# rapidshark-display-shifter-mk-2_0.net
KiCad netlist of a schematic drawn in EAGLE
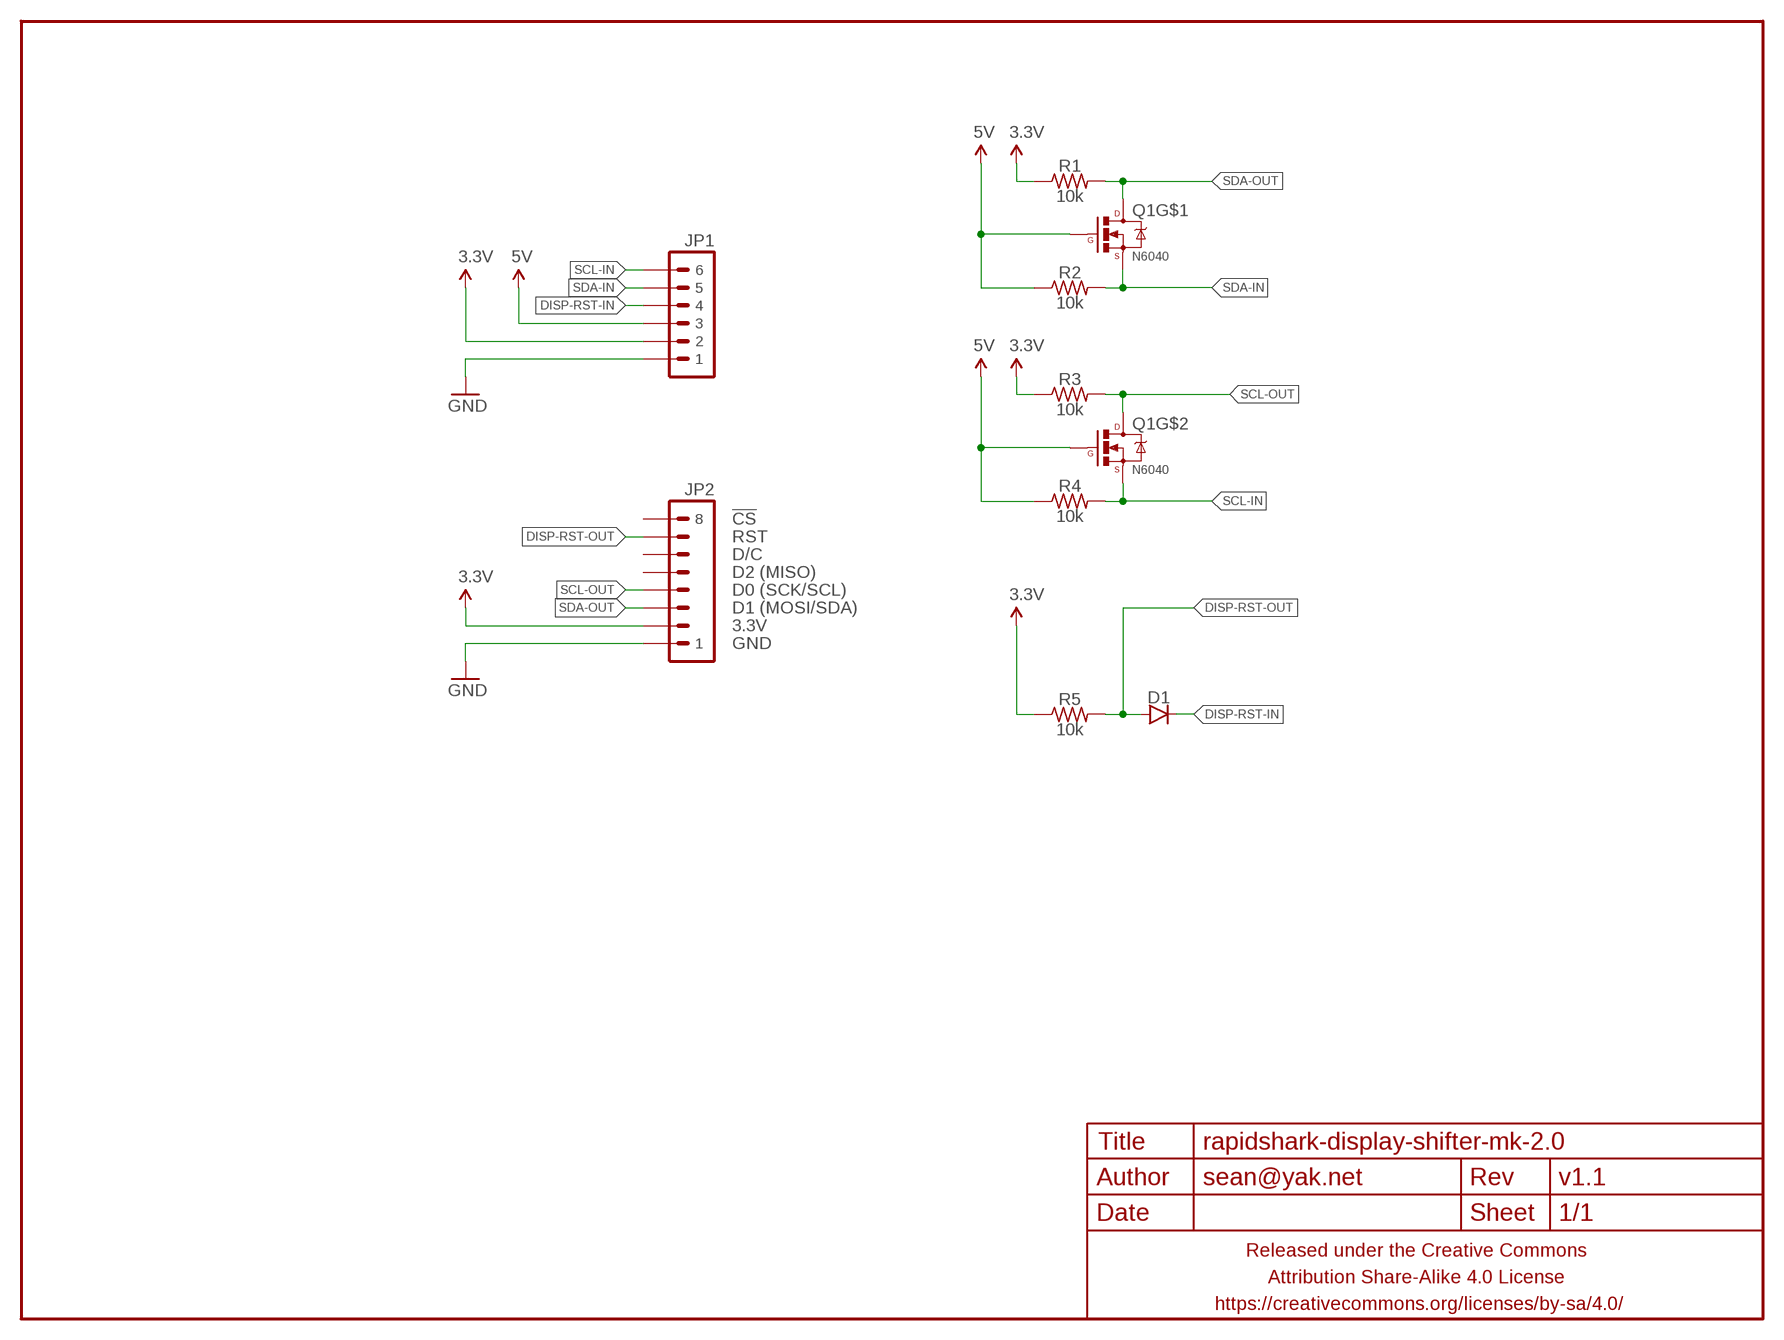
[diagram p0: schematic, sheet 1]

(export (version "E")
  (design (tool "Eeschema 10.0.6"))
  (components
    (comp (ref "D1")
      (value "DIODESMA")
      (footprint "eagle-import:SMA-DIODE")
      (libsource (lib "eagle-import") (part "DIODESMA"))
    )
    (comp (ref "FRAME1")
      (value "FRAME-LETTERNO_PACKAGE")
      (footprint "eagle-import:DUMMY")
      (fields (field (name "DESIGNER") "sean@yak.net") (field (name "VERSION") "v1.1"))
      (libsource (lib "eagle-import") (part "FRAME-LETTERNO_PACKAGE"))
    )
    (comp (ref "JP1")
      (value "M06JST-PH-PTH-VERT")
      (footprint "eagle-import:JST-6-PH-VERT-PTH")
      (libsource (lib "eagle-import") (part "M06JST-PH-PTH-VERT"))
    )
    (comp (ref "JP2")
      (value "M081X08")
      (footprint "eagle-import:1X08")
      (libsource (lib "eagle-import") (part "M081X08"))
    )
    (comp (ref "Q1")
      (value "N6040")
      (footprint "eagle-import:SO08")
      (libsource (lib "eagle-import") (part "MOSFET-NCHANNEL-DUALSOIC8"))
    )
    (comp (ref "R1")
      (value "10k")
      (footprint "eagle-import:R0805")
      (libsource (lib "eagle-import") (part "RESISTORR0805"))
    )
    (comp (ref "R2")
      (value "10k")
      (footprint "eagle-import:R0805")
      (libsource (lib "eagle-import") (part "RESISTORR0805"))
    )
    (comp (ref "R3")
      (value "10k")
      (footprint "eagle-import:R0805")
      (libsource (lib "eagle-import") (part "RESISTORR0805"))
    )
    (comp (ref "R4")
      (value "10k")
      (footprint "eagle-import:R0805")
      (libsource (lib "eagle-import") (part "RESISTORR0805"))
    )
    (comp (ref "R5")
      (value "10k")
      (footprint "eagle-import:R0805")
      (libsource (lib "eagle-import") (part "RESISTORR0805"))
    )
  )
  (nets
    (net (code "1") (name "3.3V") (class "Default")
      (node (ref "JP1") (pin "2") (pinfunction "2_2") (pintype "passive"))
      (node (ref "JP2") (pin "2") (pinfunction "2_2") (pintype "passive"))
      (node (ref "R1") (pin "1") (pinfunction "1_1") (pintype "passive"))
      (node (ref "R3") (pin "1") (pinfunction "1_1") (pintype "passive"))
      (node (ref "R5") (pin "1") (pinfunction "1_1") (pintype "passive"))
    )
    (net (code "2") (name "5V") (class "Default")
      (node (ref "JP1") (pin "3") (pinfunction "3_3") (pintype "passive"))
      (node (ref "Q1") (pin "2") (pinfunction "G_2") (pintype "passive"))
      (node (ref "Q1") (pin "4") (pinfunction "G_4") (pintype "passive"))
      (node (ref "R2") (pin "1") (pinfunction "1_1") (pintype "passive"))
      (node (ref "R4") (pin "1") (pinfunction "1_1") (pintype "passive"))
    )
    (net (code "3") (name "DISP-RST-IN") (class "Default")
      (node (ref "D1") (pin "C") (pinfunction "C_C") (pintype "passive"))
      (node (ref "JP1") (pin "4") (pinfunction "4_4") (pintype "passive"))
    )
    (net (code "4") (name "DISP-RST-OUT") (class "Default")
      (node (ref "D1") (pin "A") (pinfunction "A_A") (pintype "passive"))
      (node (ref "JP2") (pin "7") (pinfunction "7_7") (pintype "passive"))
      (node (ref "R5") (pin "2") (pinfunction "2_2") (pintype "passive"))
    )
    (net (code "5") (name "GND") (class "Default")
      (node (ref "JP1") (pin "1") (pinfunction "1_1") (pintype "passive"))
      (node (ref "JP2") (pin "1") (pinfunction "1_1") (pintype "passive"))
    )
    (net (code "6") (name "SCL-IN") (class "Default")
      (node (ref "JP1") (pin "6") (pinfunction "6_6") (pintype "passive"))
      (node (ref "Q1") (pin "3") (pinfunction "S_3") (pintype "passive"))
      (node (ref "R4") (pin "2") (pinfunction "2_2") (pintype "passive"))
    )
    (net (code "7") (name "SCL-OUT") (class "Default")
      (node (ref "JP2") (pin "4") (pinfunction "4_4") (pintype "passive"))
      (node (ref "Q1") (pin "5") (pinfunction "D_5") (pintype "passive"))
      (node (ref "Q1") (pin "6") (pinfunction "D_6") (pintype "passive"))
      (node (ref "R3") (pin "2") (pinfunction "2_2") (pintype "passive"))
    )
    (net (code "8") (name "SDA-IN") (class "Default")
      (node (ref "JP1") (pin "5") (pinfunction "5_5") (pintype "passive"))
      (node (ref "Q1") (pin "1") (pinfunction "S_1") (pintype "passive"))
      (node (ref "R2") (pin "2") (pinfunction "2_2") (pintype "passive"))
    )
    (net (code "9") (name "SDA-OUT") (class "Default")
      (node (ref "JP2") (pin "3") (pinfunction "3_3") (pintype "passive"))
      (node (ref "Q1") (pin "7") (pinfunction "D_7") (pintype "passive"))
      (node (ref "Q1") (pin "8") (pinfunction "D_8") (pintype "passive"))
      (node (ref "R1") (pin "2") (pinfunction "2_2") (pintype "passive"))
    )
    (net (code "10") (name "unconnected-(JP2-Pad5)") (class "Default")
      (node (ref "JP2") (pin "5") (pinfunction "5_5") (pintype "passive"))
    )
    (net (code "11") (name "unconnected-(JP2-Pad6)") (class "Default")
      (node (ref "JP2") (pin "6") (pinfunction "6_6") (pintype "passive"))
    )
    (net (code "12") (name "unconnected-(JP2-Pad8)") (class "Default")
      (node (ref "JP2") (pin "8") (pinfunction "8_8") (pintype "passive"))
    )
  )
)
